# lipo-charger.net
KiCad netlist of a schematic drawn in EAGLE
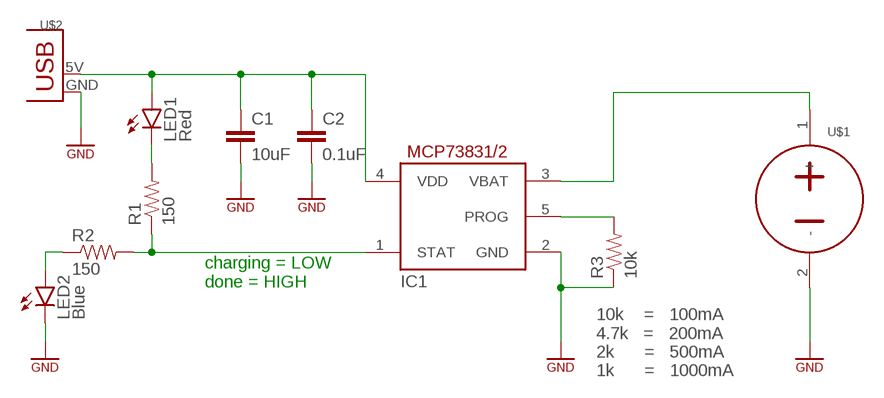
[diagram p0: schematic, sheet 1]

(export (version "E")
  (design (tool "Eeschema 10.0.6"))
  (components
    (comp (ref "C1")
      (value "10uF")
      (footprint "eagle-import:0805")
      (libsource (lib "eagle-import") (part "COMPONENT_CAP-0805"))
    )
    (comp (ref "C2")
      (value "0.1uF")
      (footprint "eagle-import:0805")
      (libsource (lib "eagle-import") (part "COMPONENT_CAP-0805"))
    )
    (comp (ref "IC1")
      (value "IC_LIPO_CHARGER")
      (footprint "eagle-import:SOT23-5")
      (libsource (lib "eagle-import") (part "IC_LIPO_CHARGER"))
    )
    (comp (ref "LED1")
      (value "Red")
      (footprint "eagle-import:CHIP-LED0805")
      (libsource (lib "eagle-import") (part "LED-0805"))
    )
    (comp (ref "LED2")
      (value "Blue")
      (footprint "eagle-import:CHIP-LED0805")
      (libsource (lib "eagle-import") (part "LED-0805"))
    )
    (comp (ref "R1")
      (value "150")
      (footprint "eagle-import:0805")
      (libsource (lib "eagle-import") (part "COMPONENT_RESISTOR-0805"))
    )
    (comp (ref "R2")
      (value "150")
      (footprint "eagle-import:0805")
      (libsource (lib "eagle-import") (part "COMPONENT_RESISTOR-0805"))
    )
    (comp (ref "R3")
      (value "10k")
      (footprint "eagle-import:0805")
      (libsource (lib "eagle-import") (part "COMPONENT_RESISTOR-0805"))
    )
    (comp (ref "U$1")
      (value "CONN_BATTERY-LIPO-HORIZ")
      (footprint "eagle-import:JST-PH-2-SMT-RA")
      (libsource (lib "eagle-import") (part "CONN_BATTERY-LIPO-HORIZ"))
    )
    (comp (ref "U$2")
      (value "CONN_USB_PCB_POWER")
      (footprint "eagle-import:USB-PCB-POWER")
      (libsource (lib "eagle-import") (part "CONN_USB_PCB_POWER"))
    )
  )
  (nets
    (net (code "1") (name "Net-(IC1-PROG)") (class "Default")
      (node (ref "IC1") (pin "5") (pinfunction "PROG_5") (pintype "input"))
      (node (ref "R3") (pin "2") (pinfunction "2_2") (pintype "passive"))
    )
    (net (code "2") (name "Net-(IC1-STAT)") (class "Default")
      (node (ref "IC1") (pin "1") (pinfunction "STAT_1") (pintype "output"))
      (node (ref "R1") (pin "1") (pinfunction "1_1") (pintype "passive"))
      (node (ref "R2") (pin "2") (pinfunction "2_2") (pintype "passive"))
    )
    (net (code "3") (name "Net-(IC1-VBAT)") (class "Default")
      (node (ref "IC1") (pin "3") (pinfunction "VBAT_3") (pintype "bidirectional"))
      (node (ref "U$1") (pin "1") (pinfunction "+_1") (pintype "bidirectional"))
    )
    (net (code "4") (name "Net-(IC1-VDD)") (class "Default")
      (node (ref "C1") (pin "1") (pinfunction "1_1") (pintype "passive"))
      (node (ref "C2") (pin "1") (pinfunction "1_1") (pintype "passive"))
      (node (ref "IC1") (pin "4") (pinfunction "VDD_4") (pintype "power_in"))
      (node (ref "LED1") (pin "A") (pinfunction "A_A") (pintype "passive"))
      (node (ref "U$2") (pin "5V") (pinfunction "VBUS_5V") (pintype "bidirectional"))
    )
    (net (code "5") (name "Net-(LED1-PadC)") (class "Default")
      (node (ref "LED1") (pin "C") (pinfunction "C_C") (pintype "passive"))
      (node (ref "R1") (pin "2") (pinfunction "2_2") (pintype "passive"))
    )
    (net (code "6") (name "Net-(LED2-PadA)") (class "Default")
      (node (ref "LED2") (pin "A") (pinfunction "A_A") (pintype "passive"))
      (node (ref "R2") (pin "1") (pinfunction "1_1") (pintype "passive"))
    )
    (net (code "7") (name "SYMBOL_GND") (class "Default")
      (node (ref "C1") (pin "2") (pinfunction "2_2") (pintype "passive"))
      (node (ref "C2") (pin "2") (pinfunction "2_2") (pintype "passive"))
      (node (ref "IC1") (pin "2") (pinfunction "GND_2") (pintype "power_in"))
      (node (ref "LED2") (pin "C") (pinfunction "C_C") (pintype "passive"))
      (node (ref "R3") (pin "1") (pinfunction "1_1") (pintype "passive"))
      (node (ref "U$1") (pin "2") (pinfunction "-_2") (pintype "bidirectional"))
      (node (ref "U$2") (pin "GND") (pinfunction "GND_GND") (pintype "bidirectional"))
    )
  )
)
